# MaxBotix-Helper.net
KiCad netlist of a schematic drawn in EAGLE
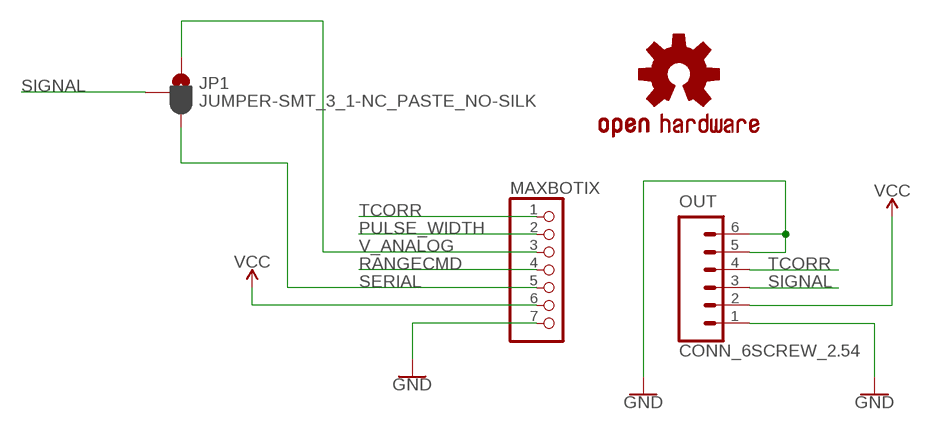
[diagram p0: schematic, sheet 1]

(export (version "E")
  (design (tool "Eeschema 10.0.6"))
  (components
    (comp (ref "JP1")
      (value "JUMPER-SMT_3_1-NC_PASTE_NO-SILK")
      (footprint "eagle-import:SMT-JUMPER_3_1-NC_PASTE_NO-SILK")
      (libsource (lib "eagle-import") (part "JUMPER-SMT_3_1-NC_PASTE_NO-SILK"))
    )
    (comp (ref "LOGO1")
      (value "OSHW-LOGOS")
      (footprint "eagle-import:OSHW-LOGO-S")
      (libsource (lib "eagle-import") (part "OSHW-LOGOS"))
    )
    (comp (ref "MAXBOTIX")
      (value "CONN_7")
      (footprint "eagle-import:1X07")
      (libsource (lib "eagle-import") (part "CONN_7"))
    )
    (comp (ref "OUT")
      (value "CONN_6SCREW_2.54")
      (footprint "eagle-import:1X06_SCREW")
      (fields (field (name "MF") "OnShore") (field (name "MPN") "OSTVN06A150"))
      (libsource (lib "eagle-import") (part "CONN_6SCREW_2.54"))
    )
  )
  (nets
    (net (code "1") (name "/PULSE_WIDTH") (class "Default")
      (node (ref "MAXBOTIX") (pin "2") (pinfunction "2_2") (pintype "passive"))
    )
    (net (code "2") (name "/RANGECMD") (class "Default")
      (node (ref "MAXBOTIX") (pin "4") (pinfunction "4_4") (pintype "passive"))
    )
    (net (code "3") (name "/SERIAL") (class "Default")
      (node (ref "JP1") (pin "3") (pinfunction "3_3") (pintype "passive"))
      (node (ref "MAXBOTIX") (pin "5") (pinfunction "5_5") (pintype "passive"))
    )
    (net (code "4") (name "/SIGNAL") (class "Default")
      (node (ref "JP1") (pin "2") (pinfunction "2_2") (pintype "passive"))
      (node (ref "OUT") (pin "3") (pinfunction "3_3") (pintype "passive"))
    )
    (net (code "5") (name "/TCORR") (class "Default")
      (node (ref "MAXBOTIX") (pin "1") (pinfunction "1_1") (pintype "passive"))
      (node (ref "OUT") (pin "4") (pinfunction "4_4") (pintype "passive"))
    )
    (net (code "6") (name "/V_ANALOG") (class "Default")
      (node (ref "JP1") (pin "1") (pinfunction "1_1") (pintype "passive"))
      (node (ref "MAXBOTIX") (pin "3") (pinfunction "3_3") (pintype "passive"))
    )
    (net (code "7") (name "GND") (class "Default")
      (node (ref "MAXBOTIX") (pin "7") (pinfunction "7_7") (pintype "passive"))
      (node (ref "OUT") (pin "1") (pinfunction "1_1") (pintype "passive"))
      (node (ref "OUT") (pin "5") (pinfunction "5_5") (pintype "passive"))
      (node (ref "OUT") (pin "6") (pinfunction "6_6") (pintype "passive"))
    )
    (net (code "8") (name "VCC") (class "Default")
      (node (ref "MAXBOTIX") (pin "6") (pinfunction "6_6") (pintype "passive"))
      (node (ref "OUT") (pin "2") (pinfunction "2_2") (pintype "passive"))
    )
  )
)
